# GNSS_Antenna.net
KiCad netlist of a schematic drawn in Altium Designer
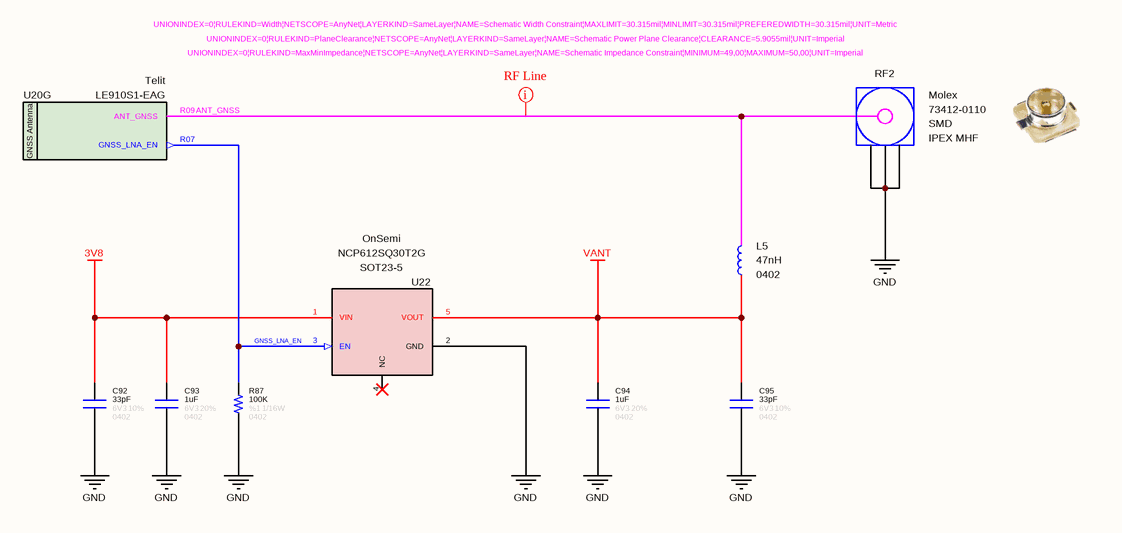
[diagram p0: GNSS Antenna.SchDoc]

(export (version "E")
  (design (tool "Eeschema 10.0.6"))
  (components
    (comp (ref "C92")
      (value "33pF")
      (footprint "CAPACITOR_0402")
      (description "Capacitor - 33pF [0402] (Ceramic)")
      (fields
        (field (name "MANUFACTURER PART NUMBER") "C0402C330J9RACAUTO")
        (field (name "TOLERANCE") "10%")
        (field (name "CASE") "0402")
        (field (name "VOLTAGE") "6V3")
      )
      (libsource (lib "Akkoyun") (part "Capacitor - 33pF [0402-6V3]"))
    )
    (comp (ref "C93")
      (value "1uF")
      (footprint "CAPACITOR_0402")
      (description "Multilayer Ceramic Capacitors - SMD - 6.3V 1uF X5R 0402 20%")
      (fields
        (field (name "MANUFACTURER PART NUMBER") "GRM153R60J105ME95D")
        (field (name "TOLERANCE") "20%")
        (field (name "CASE") "0402")
        (field (name "VOLTAGE") "6V3")
        (field (name "Comment") "Capacitor - 1uF [0402] (Ceramic)")
      )
      (libsource (lib "Akkoyun") (part "Capacitor - 1uF [0402-6V3]"))
    )
    (comp (ref "C94")
      (value "1uF")
      (footprint "CAPACITOR_0402")
      (description "Multilayer Ceramic Capacitors - SMD - 6.3V 1uF X5R 0402 20%")
      (fields
        (field (name "MANUFACTURER PART NUMBER") "GRM153R60J105ME95D")
        (field (name "TOLERANCE") "20%")
        (field (name "CASE") "0402")
        (field (name "VOLTAGE") "6V3")
        (field (name "Comment") "Capacitor - 1uF [0402] (Ceramic)")
      )
      (libsource (lib "Akkoyun") (part "Capacitor - 1uF [0402-6V3]"))
    )
    (comp (ref "C95")
      (value "33pF")
      (footprint "CAPACITOR_0402")
      (description "Capacitor - 33pF [0402] (Ceramic)")
      (fields
        (field (name "MANUFACTURER PART NUMBER") "C0402C330J9RACAUTO")
        (field (name "TOLERANCE") "10%")
        (field (name "CASE") "0402")
        (field (name "VOLTAGE") "6V3")
      )
      (libsource (lib "Akkoyun") (part "Capacitor - 33pF [0402-6V3]"))
    )
    (comp (ref "L5")
      (value "47nH")
      (footprint "INDUCTOR_0603")
      (description "RF Inductors - SMD 47 NH 2%")
      (fields
        (field (name "MANUFACTURER PART NUMBER") "LQW15AN47NG00D")
        (field (name "TOLERANCE") "2%")
        (field (name "CASE") "0402")
      )
      (libsource (lib "Akkoyun") (part "Inductor - LQW15AN47NG00D"))
    )
    (comp (ref "R87")
      (value "100K")
      (footprint "RESISTOR_0402")
      (description "Thick Film Resistors - SMD 1/16 W 100 KOhm 1%")
      (fields
        (field (name "MANUFACTURER PART NUMBER") "CRCW0402100KFKED")
        (field (name "TOLERANCE") "%1")
        (field (name "CASE") "0402")
        (field (name "POWER") "1/16W")
        (field (name "Comment") "100K - 0402 - %1 - 1/16W")
      )
      (libsource (lib "Akkoyun") (part "Resistor - 100K [0402]"))
    )
    (comp (ref "RF2")
      (value "73412-0110")
      (footprint "Connector_IPEX")
      (description "MOLEX   73412-0110   RF COAXIAL, MICROCOAXIAL, JACK, 50OHM")
      (fields
        (field (name "CONNECTOR TYPE") "IPEX MHF")
        (field (name "CASE") "SMD")
        (field (name "MANUFACTURER PART NUMBER") "73412-0110")
        (field (name "MANUFACTURER NAME") "Molex")
      )
      (libsource (lib "Akkoyun") (part "Connector - IPEX MHF"))
    )
    (comp (ref "U20")
      (value "LE910S1-EAG LTE GSM Module")
      (footprint "LE910 GSM Modem")
      (description "Telit LE910S1-EAG GPRS/GNSS Module")
      (fields
        (field (name "MANUFACTURER PART NUMBER") "LE910S1-EAG")
        (field (name "MANUFACTURER NAME") "Telit")
      )
      (libsource (lib "Akkoyun") (part "IC - LE910S1-EAG"))
    )
    (comp (ref "U22")
      (value "NCP612SQ30T2G")
      (footprint "SOT-23-5")
      (description "LDO Voltage Regulators ACMOS1 LDO REGULATOR")
      (fields
        (field (name "MANUFACTURER NAME") "OnSemi")
        (field (name "MANUFACTURER PART NUMBER") "NCP612SQ30T2G")
        (field (name "CASE") "SOT23-5")
      )
      (libsource (lib "Akkoyun") (part "IC - NCP612SQ30T2G"))
    )
  )
  (nets
    (net (code "1") (name "/ANT_GNSS") (class "Default")
      (node (ref "L5") (pin "2") (pinfunction "2_2") (pintype "passive"))
      (node (ref "RF2") (pin "1") (pinfunction "Signal_1") (pintype "passive"))
      (node (ref "U20") (pin "R09") (pinfunction "ANT_GNSS_R09") (pintype "passive"))
    )
    (net (code "2") (name "/GNSS_LNA_EN") (class "Default")
      (node (ref "R87") (pin "2") (pinfunction "2_2") (pintype "passive"))
      (node (ref "U20") (pin "R07") (pinfunction "GNSS_LNA_EN_R07") (pintype "output"))
      (node (ref "U22") (pin "3") (pinfunction "EN_3") (pintype "input"))
    )
    (net (code "3") (name "3V8") (class "Default")
      (node (ref "C92") (pin "2") (pinfunction "2_2") (pintype "passive"))
      (node (ref "C93") (pin "2") (pinfunction "2_2") (pintype "passive"))
      (node (ref "U22") (pin "1") (pinfunction "VIN_1") (pintype "power_in"))
    )
    (net (code "4") (name "GND") (class "Default")
      (node (ref "C92") (pin "1") (pinfunction "1_1") (pintype "passive"))
      (node (ref "C93") (pin "1") (pinfunction "1_1") (pintype "passive"))
      (node (ref "C94") (pin "1") (pinfunction "1_1") (pintype "passive"))
      (node (ref "C95") (pin "1") (pinfunction "1_1") (pintype "passive"))
      (node (ref "R87") (pin "1") (pinfunction "1_1") (pintype "passive"))
      (node (ref "RF2") (pin "2") (pinfunction "GND_2") (pintype "passive"))
      (node (ref "RF2") (pin "3") (pinfunction "GND_3") (pintype "passive"))
      (node (ref "RF2") (pin "4") (pinfunction "GND_4") (pintype "passive"))
      (node (ref "U22") (pin "2") (pinfunction "GND_2") (pintype "power_in"))
    )
    (net (code "5") (name "VANT") (class "Default")
      (node (ref "C94") (pin "2") (pinfunction "2_2") (pintype "passive"))
      (node (ref "C95") (pin "2") (pinfunction "2_2") (pintype "passive"))
      (node (ref "L5") (pin "1") (pinfunction "1_1") (pintype "passive"))
      (node (ref "U22") (pin "5") (pinfunction "VOUT_5") (pintype "power_in"))
    )
    (net (code "6") (name "unconnected-(U22-NC-Pad4)") (class "Default")
      (node (ref "U22") (pin "4") (pinfunction "NC_4") (pintype "passive"))
    )
    (net (code "7") (name "unconnected-(U22-NC-Pad4)") (class "Default")
      (node (ref "U22") (pin "4") (pinfunction "NC_4") (pintype "power_in+no_connect"))
    )
  )
)
